# MK12.net
KiCad netlist of a schematic drawn in EAGLE
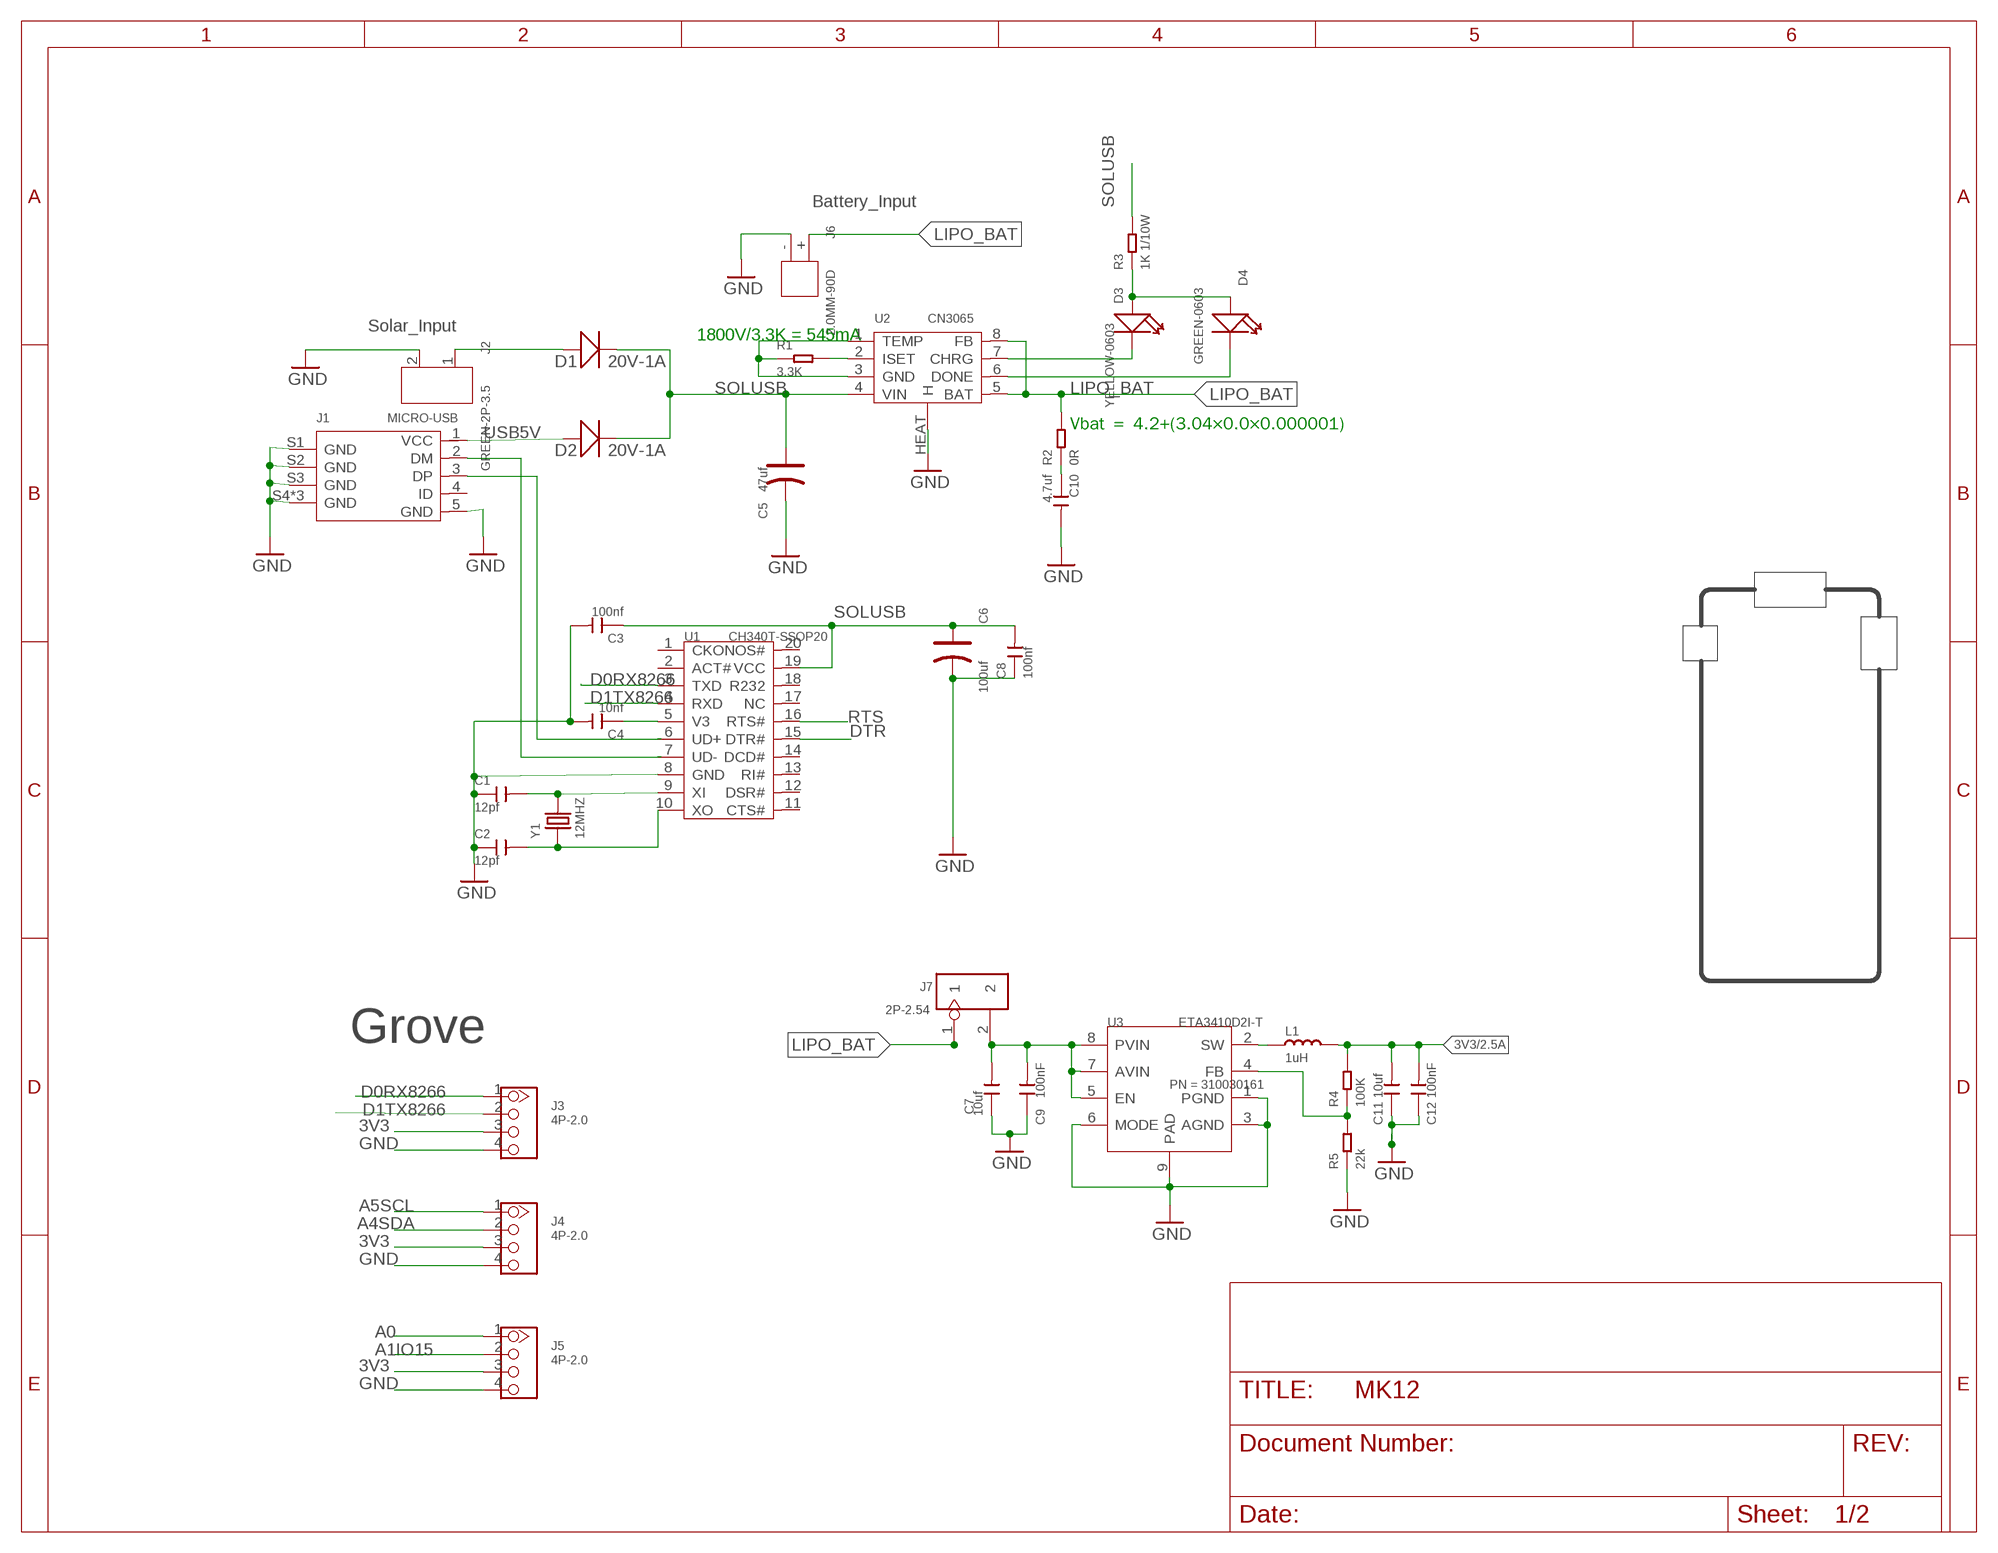
[diagram p0: schematic, sheet 1]
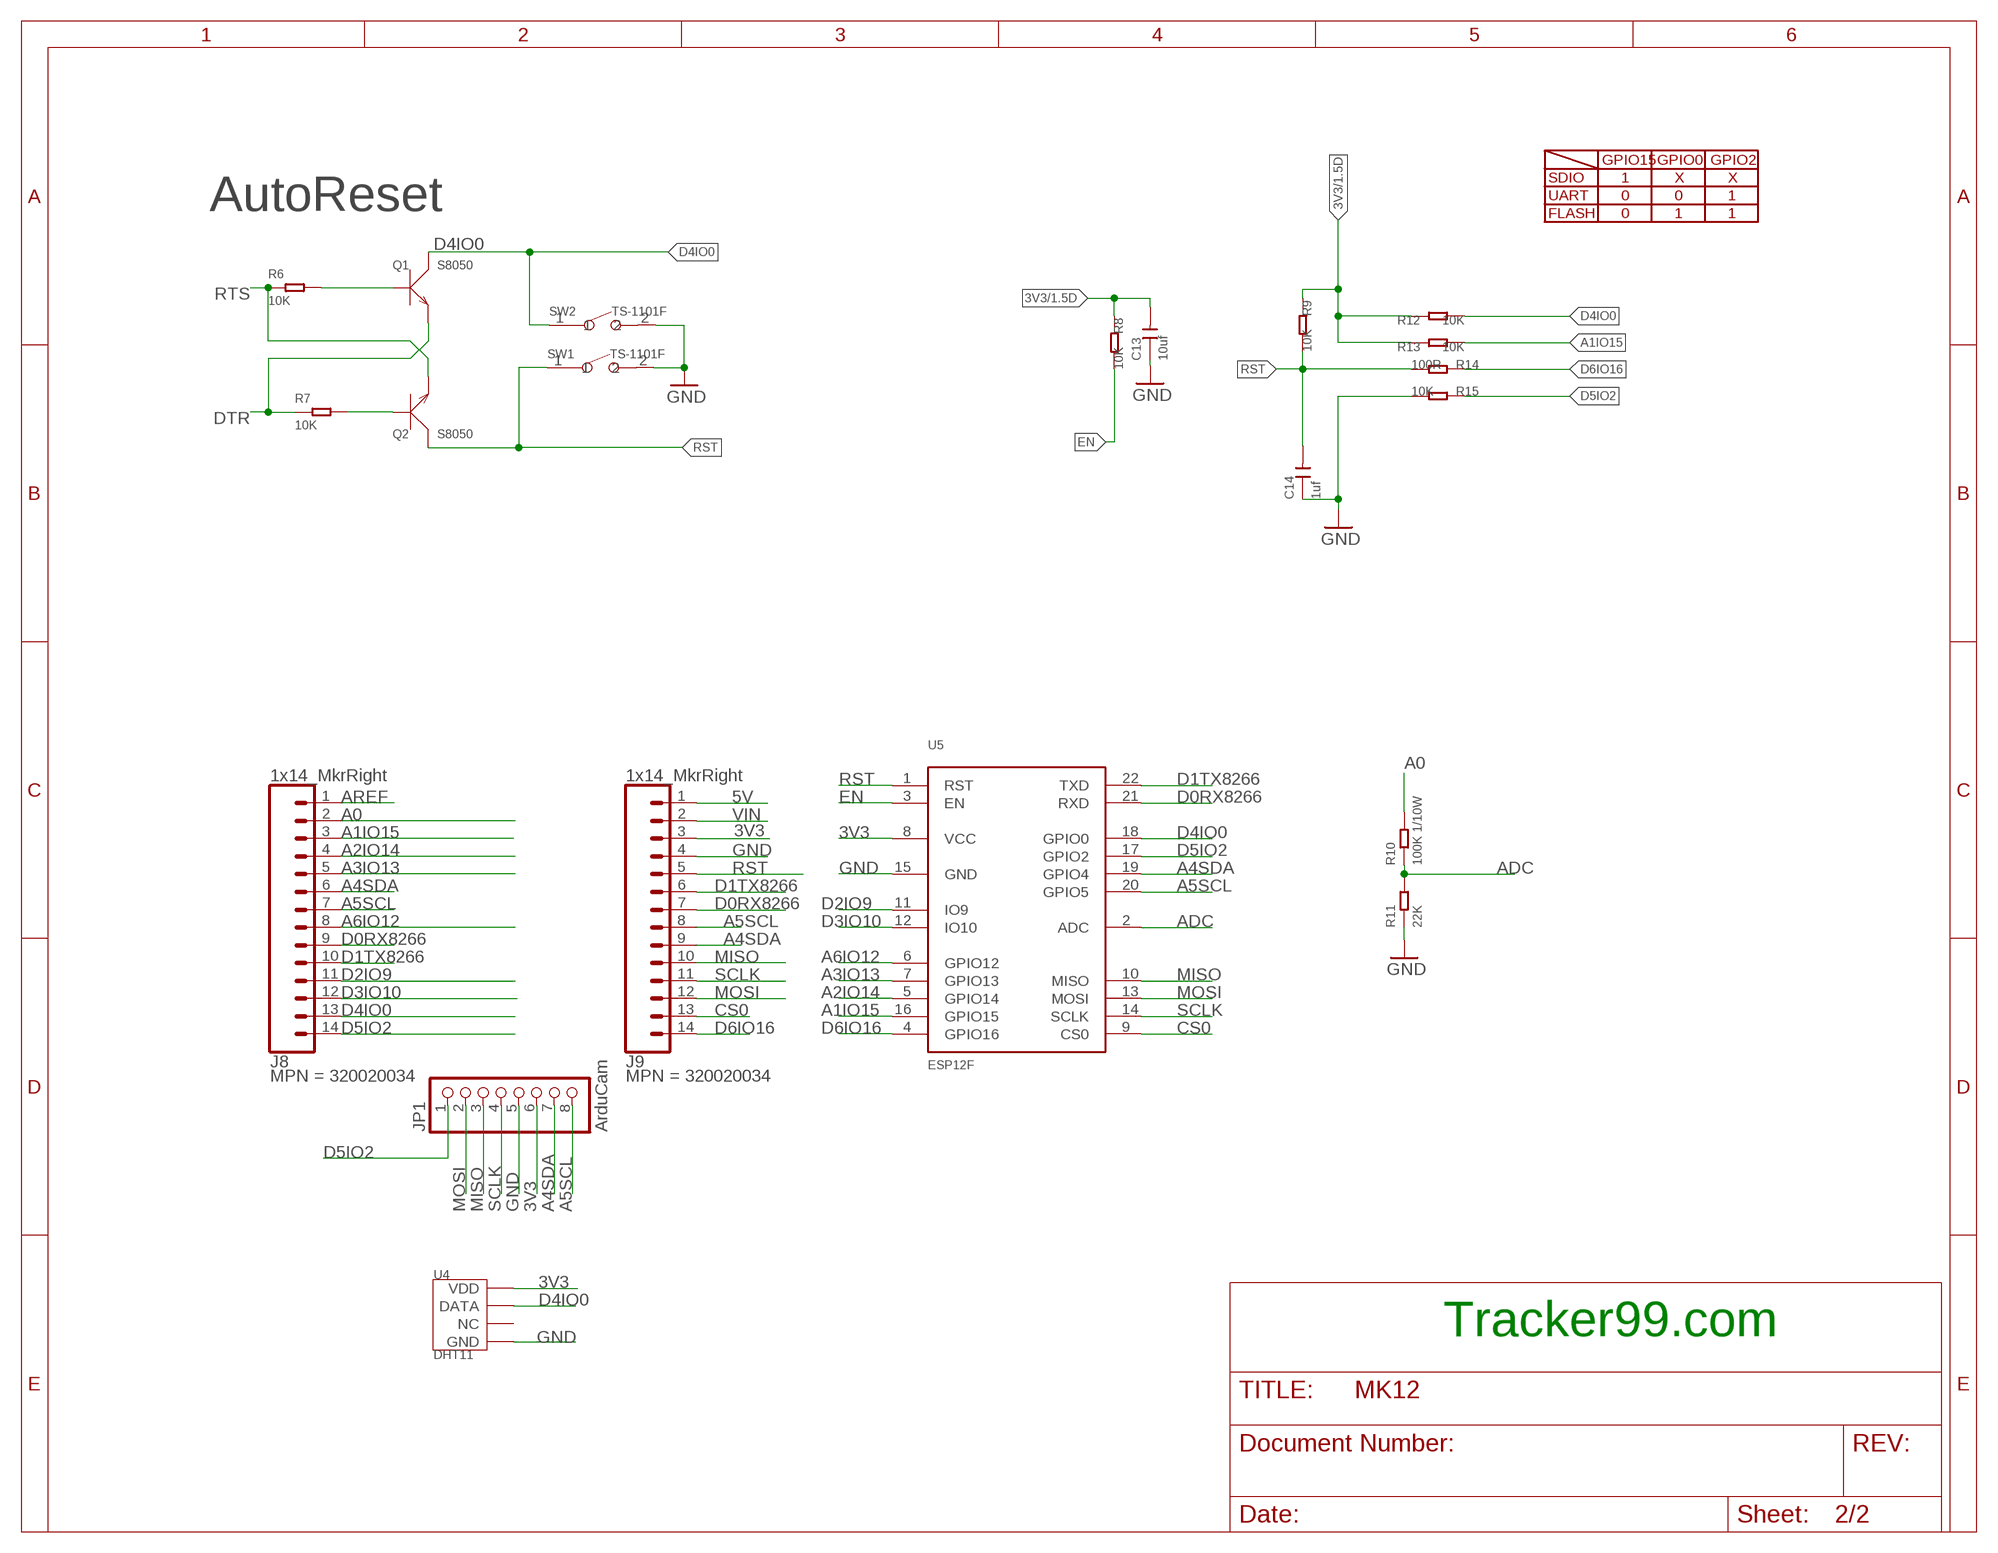
[diagram p1: schematic, sheet 2]

(export (version "E")
  (design (tool "Eeschema 10.0.6"))
  (components
    (comp (ref "C1")
      (value "12pf")
      (footprint "eagle-import:C0402")
      (fields (field (name "MPN") "CC0402JRNPO9BN120"))
      (libsource (lib "eagle-import") (part "CERAMIC-12PF-50V-5%-NPO(0402)"))
    )
    (comp (ref "C2")
      (value "12pf")
      (footprint "eagle-import:C0402")
      (fields (field (name "MPN") "CC0402JRNPO9BN120"))
      (libsource (lib "eagle-import") (part "CERAMIC-12PF-50V-5%-NPO(0402)"))
    )
    (comp (ref "C3")
      (value "100nf")
      (footprint "eagle-import:C0603")
      (fields (field (name "MPN") "CC0603KRX7R9BB104"))
      (libsource (lib "eagle-import") (part "CERAMIC-100NF-50V-10%-X7R(0603)"))
    )
    (comp (ref "C4")
      (value "10nf")
      (footprint "eagle-import:C0603")
      (fields (field (name "MPN") "CC0603KRX7R9BB103"))
      (libsource (lib "eagle-import") (part "CERAMIC-10NF-50V-10%-X7R(0603)"))
    )
    (comp (ref "C5")
      (value "47uf")
      (footprint "eagle-import:AVX-A")
      (fields (field (name "MPN") "TAJA476*006#NJ"))
      (libsource (lib "eagle-import") (part "TANTALUM-SMD-47UF-6.3V(AVX-A)"))
    )
    (comp (ref "C6")
      (value "100uf")
      (footprint "eagle-import:AVX-B")
      (fields (field (name "MPN") "TAJB107M010#NJ"))
      (libsource (lib "eagle-import") (part "TANTALUM-SMD-100UF-10V(AVX-B)"))
    )
    (comp (ref "C7")
      (value "10uf")
      (footprint "eagle-import:C0805")
      (fields (field (name "MPN") "CC0805KKX5R8BB106"))
      (libsource (lib "eagle-import") (part "CERAMIC-10UF-25V-10%-X5R(0805)"))
    )
    (comp (ref "C8")
      (value "100nf")
      (footprint "eagle-import:C0603")
      (fields (field (name "MPN") "CC0603KRX7R9BB104"))
      (libsource (lib "eagle-import") (part "CERAMIC-100NF-50V-10%-X7R(0603)"))
    )
    (comp (ref "C9")
      (value "100nF")
      (footprint "eagle-import:C0402")
      (libsource (lib "eagle-import") (part "CAP-0402"))
    )
    (comp (ref "C10")
      (value "4.7uf")
      (footprint "eagle-import:C0603")
      (fields (field (name "MPN") "CC0603KRX5R6BB475"))
      (libsource (lib "eagle-import") (part "CERAMIC-4.7UF-10V-10%-X5R(0603)"))
    )
    (comp (ref "C11")
      (value "10uf")
      (footprint "eagle-import:C0805")
      (fields (field (name "MPN") "CC0805KKX5R8BB106"))
      (libsource (lib "eagle-import") (part "CERAMIC-10UF-25V-10%-X5R(0805)"))
    )
    (comp (ref "C12")
      (value "100nF")
      (footprint "eagle-import:C0402")
      (libsource (lib "eagle-import") (part "CAP-0402"))
    )
    (comp (ref "D1")
      (value "20V-1A")
      (footprint "eagle-import:SOD-123")
      (fields (field (name "MPN") "B5819W"))
      (libsource (lib "eagle-import") (part "SMD-DIODE-SCHOTTKY-20V-1A(SOD-123)"))
    )
    (comp (ref "D2")
      (value "20V-1A")
      (footprint "eagle-import:SOD-123")
      (fields (field (name "MPN") "B5819W"))
      (libsource (lib "eagle-import") (part "SMD-DIODE-SCHOTTKY-20V-1A(SOD-123)"))
    )
    (comp (ref "D3")
      (value "YELLOW-0603")
      (footprint "eagle-import:LED-0603")
      (fields (field (name "MPN") "19-217-Y5C-AM1N1VY-3T"))
      (libsource (lib "eagle-import") (part "SMD-LED-CLEAR-YELLOW(0603)"))
    )
    (comp (ref "D4")
      (value "GREEN-0603")
      (footprint "eagle-import:LED-0603")
      (fields (field (name "MPN") "19-217-G7C-AN1P2-3T"))
      (libsource (lib "eagle-import") (part "SMD-LED-CLEAR-GREEN(0603)"))
    )
    (comp (ref "J1")
      (value "MICRO-USB")
      (footprint "eagle-import:MICRO-USB5+4P-SMD-0.65-B")
      (fields (field (name "EAGLEUP") "USB-MICROB;2.54mm"))
      (libsource (lib "eagle-import") (part "MICRO-USB5+4P'5+4P'"))
    )
    (comp (ref "J2")
      (value "GREEN-2P-3.5")
      (footprint "eagle-import:H2-3.5-7.0X7.0MM")
      (libsource (lib "eagle-import") (part "SCREW-TERMINAL-GREEN(2P-3.5)"))
    )
    (comp (ref "J3")
      (value "4P-2.0")
      (footprint "eagle-import:HW4-2.0")
      (libsource (lib "eagle-import") (part "GROVE-CONNECTOR-DIP(4P-2.0)"))
    )
    (comp (ref "J4")
      (value "4P-2.0")
      (footprint "eagle-import:HW4-2.0")
      (libsource (lib "eagle-import") (part "GROVE-CONNECTOR-DIP(4P-2.0)"))
    )
    (comp (ref "J5")
      (value "4P-2.0")
      (footprint "eagle-import:HW4-2.0")
      (libsource (lib "eagle-import") (part "GROVE-CONNECTOR-DIP(4P-2.0)"))
    )
    (comp (ref "J6")
      (value "2.0MM-90D")
      (footprint "eagle-import:H2-2.0-90D")
      (libsource (lib "eagle-import") (part "CONN-HEADER-PH-SIDE-(2P-2.0MM)'90D'"))
    )
    (comp (ref "J7")
      (value "2P-2.54")
      (footprint "eagle-import:H2-2.54")
      (fields (field (name "MPN") "P125-1102A0BS116A3"))
      (libsource (lib "eagle-import") (part "DIP-WHITE-MALE-HEADER-VERT(2P-2.54)"))
    )
    (comp (ref "L1")
      (value "1uH")
      (footprint "eagle-import:L0603")
      (libsource (lib "eagle-import") (part "INDUCTOR/FERRITE-BEAD'0603'"))
    )
    (comp (ref "R1")
      (value "3.3K")
      (footprint "eagle-import:R0603")
      (libsource (lib "eagle-import") (part "SMD-RES-3.3K-5%-1/10W(0603)"))
    )
    (comp (ref "R2")
      (value "0R")
      (footprint "eagle-import:R0603")
      (fields (field (name "MPN") "RC0603JR-070RL"))
      (libsource (lib "eagle-import") (part "SMD-RES-0R-5%-1/10W(0603)"))
    )
    (comp (ref "R3")
      (value "1K 1/10W")
      (footprint "eagle-import:R0603")
      (fields (field (name "MPN") "RC0603JR-071KL"))
      (libsource (lib "eagle-import") (part "SMD-RES-1K-5%-1/10W(0603)"))
    )
    (comp (ref "R4")
      (value "100K")
      (footprint "eagle-import:R0402")
      (fields (field (name "MPN") "RC0402FR-07100KL"))
      (libsource (lib "eagle-import") (part "SMD-RES-100K-1%-1/16W(0402)"))
    )
    (comp (ref "R5")
      (value "22k")
      (footprint "eagle-import:R0402")
      (fields (field (name "MPN") "RC0402FR-0722KL"))
      (libsource (lib "eagle-import") (part "SMD-RES-22K-1%-1/16W(0402)"))
    )
    (comp (ref "U1")
      (value "CH340T-SSOP20")
      (footprint "eagle-import:SSOP20-0.65-7.6X5.2MM")
      (fields (field (name "MPN") "CH340T"))
      (libsource (lib "eagle-import") (part "INTERFACE-CH340T(SSOP20)"))
    )
    (comp (ref "U2")
      (value "CN3065")
      (footprint "eagle-import:DFN-8")
      (libsource (lib "eagle-import") (part "PMIC-CN3065-DFN8"))
    )
    (comp (ref "U3")
      (value "ETA3410D2I-T")
      (footprint "eagle-import:DFN8G-0.5-2X2MM")
      (fields (field (name "PN") "310030161"))
      (libsource (lib "eagle-import") (part "CONVERTER-ETA3410"))
    )
    (comp (ref "Y1")
      (value "12MHZ")
      (footprint "eagle-import:X2-SMD-5.0X3.2X1.3MM")
      (fields (field (name "MPN") "5032/2P"))
      (libsource (lib "eagle-import") (part "SMD-CRYSTAL-12MHZ-20PF-20PPM-40R(2P-5.0X3.2MM)"))
    )
    (comp (ref "C13")
      (value "10uf")
      (footprint "eagle-import:C0603")
      (fields (field (name "MPN") "CC0603KRX5R6BB106"))
      (libsource (lib "eagle-import") (part "CERAMIC-10UF-10V-10%-X5R(0603)"))
    )
    (comp (ref "C14")
      (value "1uf")
      (footprint "eagle-import:C0603")
      (fields (field (name "MPN") "CC0603KRX7R8BB105"))
      (libsource (lib "eagle-import") (part "CERAMIC-1UF-25V-10%-X7R(0603)"))
    )
    (comp (ref "J8")
      (value "1x14_MkrRight")
      (footprint "eagle-import:1X14_LOCK")
      (fields (field (name "MPN") "320020034"))
      (libsource (lib "eagle-import") (part "CONN_14LOCK"))
    )
    (comp (ref "J9")
      (value "1x14_MkrRight")
      (footprint "eagle-import:1X14_LOCK")
      (fields (field (name "MPN") "320020034"))
      (libsource (lib "eagle-import") (part "CONN_14LOCK"))
    )
    (comp (ref "JP1")
      (value "ArduCam")
      (footprint "eagle-import:MILLER_1X08-LOCK")
      (libsource (lib "eagle-import") (part "MILLER_PINHD-1X8LOCK"))
    )
    (comp (ref "Q1")
      (value "S8050")
      (footprint "eagle-import:SOT-23")
      (libsource (lib "eagle-import") (part "SMD-TRANSISTORS-NPN-25V-500MW-S8050(SOT-23)"))
    )
    (comp (ref "Q2")
      (value "S8050")
      (footprint "eagle-import:SOT-23")
      (libsource (lib "eagle-import") (part "SMD-TRANSISTORS-NPN-25V-500MW-S8050(SOT-23)"))
    )
    (comp (ref "R6")
      (value "10K")
      (footprint "eagle-import:R0402")
      (fields (field (name "MPN") "RC0402JR-0710KL"))
      (libsource (lib "eagle-import") (part "SMD-RES-10K-5%-1/(0402)"))
    )
    (comp (ref "R7")
      (value "10K")
      (footprint "eagle-import:R0402")
      (fields (field (name "MPN") "RC0402JR-0710KL"))
      (libsource (lib "eagle-import") (part "SMD-RES-10K-5%-1/(0402)"))
    )
    (comp (ref "R8")
      (value "10K")
      (footprint "eagle-import:SEEED-RESISTOR_R0402")
      (fields (field (name "MPN") "RC0402JR-0710KL"))
      (libsource (lib "eagle-import") (part "SEEED-RESISTOR_SMD-RES-10K-5%-1/(0402)"))
    )
    (comp (ref "R9")
      (value "10K")
      (footprint "eagle-import:SEEED-RESISTOR_R0402")
      (fields (field (name "MPN") "RC0402JR-0710KL"))
      (libsource (lib "eagle-import") (part "SEEED-RESISTOR_SMD-RES-10K-5%-1/(0402)"))
    )
    (comp (ref "R10")
      (value "100K 1/10W")
      (footprint "eagle-import:R0603")
      (fields (field (name "MPN") "RC0603JR-07100KL"))
      (libsource (lib "eagle-import") (part "SMD-RES-100K-5%-1/10W(0603)"))
    )
    (comp (ref "R11")
      (value "22K")
      (footprint "eagle-import:R0603")
      (fields (field (name "MPN") "RC0603JR-0722KL"))
      (libsource (lib "eagle-import") (part "SMD-RES-22K-5%-1/10W(0603)"))
    )
    (comp (ref "R12")
      (value "10K")
      (footprint "eagle-import:SEEED-RESISTOR_R0402")
      (fields (field (name "MPN") "RC0402JR-0710KL"))
      (libsource (lib "eagle-import") (part "SEEED-RESISTOR_SMD-RES-10K-5%-1/(0402)"))
    )
    (comp (ref "R13")
      (value "10K")
      (footprint "eagle-import:SEEED-RESISTOR_R0402")
      (fields (field (name "MPN") "RC0402JR-0710KL"))
      (libsource (lib "eagle-import") (part "SEEED-RESISTOR_SMD-RES-10K-5%-1/(0402)"))
    )
    (comp (ref "R14")
      (value "100R")
      (footprint "eagle-import:R0603")
      (fields (field (name "MPN") "RC0603JR-07100RL"))
      (libsource (lib "eagle-import") (part "SMD-RES-100R-5%-1/10W(0603)"))
    )
    (comp (ref "R15")
      (value "10K")
      (footprint "eagle-import:SEEED-RESISTOR_R0402")
      (fields (field (name "MPN") "RC0402JR-0710KL"))
      (libsource (lib "eagle-import") (part "SEEED-RESISTOR_SMD-RES-10K-5%-1/(0402)"))
    )
    (comp (ref "SW1")
      (value "TS-1101F")
      (footprint "eagle-import:SW2-5.0-6.0X3.0X4.3MM")
      (libsource (lib "eagle-import") (part "DIP-BUTTON(2P-6.0X3.0X4.3MM)-TS-1101F"))
    )
    (comp (ref "SW2")
      (value "TS-1101F")
      (footprint "eagle-import:SW2-5.0-6.0X3.0X4.3MM")
      (libsource (lib "eagle-import") (part "DIP-BUTTON(2P-6.0X3.0X4.3MM)-TS-1101F"))
    )
    (comp (ref "U4")
      (value "DHT11")
      (footprint "eagle-import:SNR4-2.54-15.5X12.0X5.5MM")
      (libsource (lib "eagle-import") (part "TEM-HUM-DHT11(4P-15.5X12.0MM)"))
    )
    (comp (ref "U5")
      (value "ESP12F")
      (footprint "eagle-import:ESP-12F")
      (libsource (lib "eagle-import") (part "ESP-12F"))
    )
  )
  (nets
    (net (code "1") (name "3V3") (class "Default")
      (node (ref "C11") (pin "2") (pinfunction "2_2") (pintype "passive"))
      (node (ref "C12") (pin "2") (pinfunction "2_2") (pintype "passive"))
      (node (ref "C13") (pin "2") (pinfunction "2_2") (pintype "passive"))
      (node (ref "J3") (pin "3") (pinfunction "3_3") (pintype "bidirectional"))
      (node (ref "J4") (pin "3") (pinfunction "3_3") (pintype "bidirectional"))
      (node (ref "J5") (pin "3") (pinfunction "3_3") (pintype "bidirectional"))
      (node (ref "J9") (pin "3") (pinfunction "3_3") (pintype "passive"))
      (node (ref "JP1") (pin "6") (pinfunction "6_6") (pintype "passive"))
      (node (ref "L1") (pin "2") (pinfunction "2_2") (pintype "passive"))
      (node (ref "R12") (pin "1") (pinfunction "1_1") (pintype "passive"))
      (node (ref "R13") (pin "1") (pinfunction "1_1") (pintype "passive"))
      (node (ref "R4") (pin "2") (pinfunction "2_2") (pintype "passive"))
      (node (ref "R8") (pin "1") (pinfunction "1_1") (pintype "passive"))
      (node (ref "R9") (pin "1") (pinfunction "1_1") (pintype "passive"))
      (node (ref "U4") (pin "1") (pinfunction "VDD_1") (pintype "power_in"))
      (node (ref "U5") (pin "8") (pinfunction "VCC_8") (pintype "bidirectional"))
    )
    (net (code "2") (name "5V") (class "Default")
      (node (ref "J9") (pin "1") (pinfunction "1_1") (pintype "passive"))
    )
    (net (code "3") (name "A0") (class "Default")
      (node (ref "J5") (pin "1") (pinfunction "1_1") (pintype "bidirectional"))
      (node (ref "J8") (pin "2") (pinfunction "2_2") (pintype "passive"))
      (node (ref "R10") (pin "2") (pinfunction "2_2") (pintype "passive"))
    )
    (net (code "4") (name "A1IO15") (class "Default")
      (node (ref "J5") (pin "2") (pinfunction "2_2") (pintype "bidirectional"))
      (node (ref "J8") (pin "3") (pinfunction "3_3") (pintype "passive"))
      (node (ref "R13") (pin "2") (pinfunction "2_2") (pintype "passive"))
      (node (ref "U5") (pin "16") (pinfunction "GPIO15_16") (pintype "bidirectional"))
    )
    (net (code "5") (name "A2IO14") (class "Default")
      (node (ref "J8") (pin "4") (pinfunction "4_4") (pintype "passive"))
      (node (ref "U5") (pin "5") (pinfunction "GPIO14_5") (pintype "bidirectional"))
    )
    (net (code "6") (name "A3IO13") (class "Default")
      (node (ref "J8") (pin "5") (pinfunction "5_5") (pintype "passive"))
      (node (ref "U5") (pin "7") (pinfunction "GPIO13_7") (pintype "bidirectional"))
    )
    (net (code "7") (name "A4SDA") (class "Default")
      (node (ref "J4") (pin "2") (pinfunction "2_2") (pintype "bidirectional"))
      (node (ref "J8") (pin "6") (pinfunction "6_6") (pintype "passive"))
      (node (ref "J9") (pin "9") (pinfunction "9_9") (pintype "passive"))
      (node (ref "JP1") (pin "7") (pinfunction "7_7") (pintype "passive"))
      (node (ref "U5") (pin "19") (pinfunction "GPIO4_19") (pintype "bidirectional"))
    )
    (net (code "8") (name "A5SCL") (class "Default")
      (node (ref "J4") (pin "1") (pinfunction "1_1") (pintype "bidirectional"))
      (node (ref "J8") (pin "7") (pinfunction "7_7") (pintype "passive"))
      (node (ref "J9") (pin "8") (pinfunction "8_8") (pintype "passive"))
      (node (ref "JP1") (pin "8") (pinfunction "8_8") (pintype "passive"))
      (node (ref "U5") (pin "20") (pinfunction "GPIO5_20") (pintype "bidirectional"))
    )
    (net (code "9") (name "A6IO12") (class "Default")
      (node (ref "J8") (pin "8") (pinfunction "8_8") (pintype "passive"))
      (node (ref "U5") (pin "6") (pinfunction "GPIO12_6") (pintype "bidirectional"))
    )
    (net (code "10") (name "ADC") (class "Default")
      (node (ref "R10") (pin "1") (pinfunction "1_1") (pintype "passive"))
      (node (ref "R11") (pin "2") (pinfunction "2_2") (pintype "passive"))
      (node (ref "U5") (pin "2") (pinfunction "ADC_2") (pintype "bidirectional"))
    )
    (net (code "11") (name "AREF") (class "Default")
      (node (ref "J8") (pin "1") (pinfunction "1_1") (pintype "passive"))
    )
    (net (code "12") (name "CS0") (class "Default")
      (node (ref "J9") (pin "13") (pinfunction "13_13") (pintype "passive"))
      (node (ref "U5") (pin "9") (pinfunction "CS0_9") (pintype "bidirectional"))
    )
    (net (code "13") (name "D0RX8266") (class "Default")
      (node (ref "J3") (pin "1") (pinfunction "1_1") (pintype "bidirectional"))
      (node (ref "J8") (pin "9") (pinfunction "9_9") (pintype "passive"))
      (node (ref "J9") (pin "7") (pinfunction "7_7") (pintype "passive"))
      (node (ref "U1") (pin "3") (pinfunction "TXD_3") (pintype "output"))
      (node (ref "U5") (pin "21") (pinfunction "RXD_21") (pintype "bidirectional"))
    )
    (net (code "14") (name "D1TX8266") (class "Default")
      (node (ref "J3") (pin "2") (pinfunction "2_2") (pintype "bidirectional"))
      (node (ref "J8") (pin "10") (pinfunction "10_10") (pintype "passive"))
      (node (ref "J9") (pin "6") (pinfunction "6_6") (pintype "passive"))
      (node (ref "U1") (pin "4") (pinfunction "RXD_4") (pintype "input"))
      (node (ref "U5") (pin "22") (pinfunction "TXD_22") (pintype "bidirectional"))
    )
    (net (code "15") (name "D2IO9") (class "Default")
      (node (ref "J8") (pin "11") (pinfunction "11_11") (pintype "passive"))
      (node (ref "U5") (pin "11") (pinfunction "IO9_11") (pintype "bidirectional"))
    )
    (net (code "16") (name "D3IO10") (class "Default")
      (node (ref "J8") (pin "12") (pinfunction "12_12") (pintype "passive"))
      (node (ref "U5") (pin "12") (pinfunction "IO10_12") (pintype "bidirectional"))
    )
    (net (code "17") (name "D4IO0") (class "Default")
      (node (ref "J8") (pin "13") (pinfunction "13_13") (pintype "passive"))
      (node (ref "Q1") (pin "3") (pinfunction "C_3") (pintype "passive"))
      (node (ref "R12") (pin "2") (pinfunction "2_2") (pintype "passive"))
      (node (ref "SW2") (pin "1") (pinfunction "1_1") (pintype "bidirectional"))
      (node (ref "U4") (pin "2") (pinfunction "DATA_2") (pintype "bidirectional"))
      (node (ref "U5") (pin "18") (pinfunction "GPIO0_18") (pintype "bidirectional"))
    )
    (net (code "18") (name "D5IO2") (class "Default")
      (node (ref "J8") (pin "14") (pinfunction "14_14") (pintype "passive"))
      (node (ref "JP1") (pin "1") (pinfunction "1_1") (pintype "passive"))
      (node (ref "R15") (pin "1") (pinfunction "1_1") (pintype "passive"))
      (node (ref "U5") (pin "17") (pinfunction "GPIO2_17") (pintype "bidirectional"))
    )
    (net (code "19") (name "D6IO16") (class "Default")
      (node (ref "J9") (pin "14") (pinfunction "14_14") (pintype "passive"))
      (node (ref "R14") (pin "1") (pinfunction "1_1") (pintype "passive"))
      (node (ref "U5") (pin "4") (pinfunction "GPIO16_4") (pintype "bidirectional"))
    )
    (net (code "20") (name "DTR") (class "Default")
      (node (ref "Q1") (pin "2") (pinfunction "E_2") (pintype "passive"))
      (node (ref "R7") (pin "1") (pinfunction "1_1") (pintype "passive"))
      (node (ref "U1") (pin "15") (pinfunction "DTR#_15") (pintype "output"))
    )
    (net (code "21") (name "EN") (class "Default")
      (node (ref "R8") (pin "2") (pinfunction "2_2") (pintype "passive"))
      (node (ref "U5") (pin "3") (pinfunction "EN_3") (pintype "bidirectional"))
    )
    (net (code "22") (name "GND") (class "Default")
      (node (ref "C1") (pin "1") (pinfunction "1_1") (pintype "passive"))
      (node (ref "C10") (pin "2") (pinfunction "2_2") (pintype "passive"))
      (node (ref "C11") (pin "1") (pinfunction "1_1") (pintype "passive"))
      (node (ref "C12") (pin "1") (pinfunction "1_1") (pintype "passive"))
      (node (ref "C13") (pin "1") (pinfunction "1_1") (pintype "passive"))
      (node (ref "C14") (pin "1") (pinfunction "1_1") (pintype "passive"))
      (node (ref "C2") (pin "1") (pinfunction "1_1") (pintype "passive"))
      (node (ref "C3") (pin "2") (pinfunction "2_2") (pintype "passive"))
      (node (ref "C4") (pin "2") (pinfunction "2_2") (pintype "passive"))
      (node (ref "C5") (pin "-") (pinfunction "-_-") (pintype "passive"))
      (node (ref "C6") (pin "-") (pinfunction "-_-") (pintype "passive"))
      (node (ref "C7") (pin "1") (pinfunction "1_1") (pintype "passive"))
      (node (ref "C8") (pin "1") (pinfunction "1_1") (pintype "passive"))
      (node (ref "C9") (pin "1") (pinfunction "1_1") (pintype "passive"))
      (node (ref "J1") (pin "5") (pinfunction "GND_5") (pintype "bidirectional"))
      (node (ref "J1") (pin "S1") (pinfunction "GND_S1") (pintype "bidirectional"))
      (node (ref "J1") (pin "S2") (pinfunction "GND_S2") (pintype "bidirectional"))
      (node (ref "J1") (pin "S3") (pinfunction "GND_S3") (pintype "bidirectional"))
      (node (ref "J1") (pin "S4") (pinfunction "GND_S4") (pintype "bidirectional"))
      (node (ref "J1") (pin "S5") (pinfunction "GND_S5") (pintype "bidirectional"))
      (node (ref "J1") (pin "S6") (pinfunction "GND_S6") (pintype "bidirectional"))
      (node (ref "J2") (pin "2") (pinfunction "2_2") (pintype "bidirectional"))
      (node (ref "J3") (pin "4") (pinfunction "4_4") (pintype "bidirectional"))
      (node (ref "J4") (pin "4") (pinfunction "4_4") (pintype "bidirectional"))
      (node (ref "J5") (pin "4") (pinfunction "4_4") (pintype "bidirectional"))
      (node (ref "J6") (pin "-") (pinfunction "P$2_-") (pintype "bidirectional"))
      (node (ref "J9") (pin "4") (pinfunction "4_4") (pintype "passive"))
      (node (ref "JP1") (pin "5") (pinfunction "5_5") (pintype "passive"))
      (node (ref "R1") (pin "1") (pinfunction "1_1") (pintype "passive"))
      (node (ref "R11") (pin "1") (pinfunction "1_1") (pintype "passive"))
      (node (ref "R15") (pin "2") (pinfunction "2_2") (pintype "passive"))
      (node (ref "R5") (pin "1") (pinfunction "1_1") (pintype "passive"))
      (node (ref "SW1") (pin "2") (pinfunction "2_2") (pintype "bidirectional"))
      (node (ref "SW2") (pin "2") (pinfunction "2_2") (pintype "bidirectional"))
      (node (ref "U1") (pin "8") (pinfunction "GND_8") (pintype "power_in"))
      (node (ref "U2") (pin "1") (pinfunction "TEMP_1") (pintype "input"))
      (node (ref "U2") (pin "3") (pinfunction "GND_3") (pintype "power_in"))
      (node (ref "U2") (pin "HEAT") (pinfunction "H_HEAT") (pintype "bidirectional"))
      (node (ref "U3") (pin "1") (pinfunction "PGND_1") (pintype "bidirectional"))
      (node (ref "U3") (pin "3") (pinfunction "AGND_3") (pintype "bidirectional"))
      (node (ref "U3") (pin "6") (pinfunction "MODE_6") (pintype "bidirectional"))
      (node (ref "U3") (pin "9") (pinfunction "PAD_9") (pintype "bidirectional"))
      (node (ref "U4") (pin "4") (pinfunction "GND_4") (pintype "power_in"))
      (node (ref "U5") (pin "15") (pinfunction "GND_15") (pintype "bidirectional"))
    )
    (net (code "23") (name "LIPO_BAT") (class "Default")
      (node (ref "J6") (pin "+") (pinfunction "P$1_+") (pintype "bidirectional"))
      (node (ref "J7") (pin "1") (pinfunction "1_1") (pintype "bidirectional"))
      (node (ref "R2") (pin "2") (pinfunction "2_2") (pintype "passive"))
      (node (ref "U2") (pin "5") (pinfunction "BAT_5") (pintype "bidirectional"))
      (node (ref "U2") (pin "8") (pinfunction "FB_8") (pintype "input"))
    )
    (net (code "24") (name "MISO") (class "Default")
      (node (ref "J9") (pin "10") (pinfunction "10_10") (pintype "passive"))
      (node (ref "JP1") (pin "3") (pinfunction "3_3") (pintype "passive"))
      (node (ref "U5") (pin "10") (pinfunction "MISO_10") (pintype "bidirectional"))
    )
    (net (code "25") (name "MOSI") (class "Default")
      (node (ref "J9") (pin "12") (pinfunction "12_12") (pintype "passive"))
      (node (ref "JP1") (pin "2") (pinfunction "2_2") (pintype "passive"))
      (node (ref "U5") (pin "13") (pinfunction "MOSI_13") (pintype "bidirectional"))
    )
    (net (code "26") (name "NOS#") (class "Default")
      (node (ref "U1") (pin "20") (pinfunction "NOS#_20") (pintype "power_in"))
    )
    (net (code "27") (name "Net-(C10-Pad1)") (class "Default")
      (node (ref "C10") (pin "1") (pinfunction "1_1") (pintype "passive"))
      (node (ref "R2") (pin "1") (pinfunction "1_1") (pintype "passive"))
    )
    (net (code "28") (name "Net-(D1-Pad+)") (class "Default")
      (node (ref "D1") (pin "+") (pinfunction "+_+") (pintype "passive"))
      (node (ref "J2") (pin "1") (pinfunction "1_1") (pintype "bidirectional"))
    )
    (net (code "29") (name "Net-(D3-Pad+)") (class "Default")
      (node (ref "D3") (pin "+") (pinfunction "+_+") (pintype "passive"))
      (node (ref "D4") (pin "+") (pinfunction "+_+") (pintype "passive"))
      (node (ref "R3") (pin "1") (pinfunction "1_1") (pintype "passive"))
    )
    (net (code "30") (name "Net-(J1-DM)") (class "Default")
      (node (ref "J1") (pin "2") (pinfunction "DM_2") (pintype "bidirectional"))
      (node (ref "U1") (pin "7") (pinfunction "UD-_7") (pintype "bidirectional"))
    )
    (net (code "31") (name "Net-(J1-DP)") (class "Default")
      (node (ref "J1") (pin "3") (pinfunction "DP_3") (pintype "bidirectional"))
      (node (ref "U1") (pin "6") (pinfunction "UD+_6") (pintype "bidirectional"))
    )
    (net (code "32") (name "Net-(Q1-B)") (class "Default")
      (node (ref "Q1") (pin "1") (pinfunction "B_1") (pintype "passive"))
      (node (ref "R6") (pin "2") (pinfunction "2_2") (pintype "passive"))
    )
    (net (code "33") (name "Net-(Q2-B)") (class "Default")
      (node (ref "Q2") (pin "1") (pinfunction "B_1") (pintype "passive"))
      (node (ref "R7") (pin "2") (pinfunction "2_2") (pintype "passive"))
    )
    (net (code "34") (name "Net-(U1-V3)") (class "Default")
      (node (ref "C4") (pin "1") (pinfunction "1_1") (pintype "passive"))
      (node (ref "U1") (pin "5") (pinfunction "V3_5") (pintype "power_in"))
    )
    (net (code "35") (name "Net-(U1-XI)") (class "Default")
      (node (ref "C1") (pin "2") (pinfunction "2_2") (pintype "passive"))
      (node (ref "U1") (pin "9") (pinfunction "XI_9") (pintype "input"))
      (node (ref "Y1") (pin "2") (pinfunction "2_2") (pintype "passive"))
    )
    (net (code "36") (name "Net-(U1-XO)") (class "Default")
      (node (ref "C2") (pin "2") (pinfunction "2_2") (pintype "passive"))
      (node (ref "U1") (pin "10") (pinfunction "XO_10") (pintype "output"))
      (node (ref "Y1") (pin "1") (pinfunction "1_1") (pintype "passive"))
    )
    (net (code "37") (name "Net-(U2-CHRG)") (class "Default")
      (node (ref "D3") (pin "-") (pinfunction "-_-") (pintype "passive"))
      (node (ref "U2") (pin "7") (pinfunction "CHRG_7") (pintype "bidirectional"))
    )
    (net (code "38") (name "Net-(U2-DONE)") (class "Default")
      (node (ref "D4") (pin "-") (pinfunction "-_-") (pintype "passive"))
      (node (ref "U2") (pin "6") (pinfunction "DONE_6") (pintype "bidirectional"))
    )
    (net (code "39") (name "Net-(U2-ISET)") (class "Default")
      (node (ref "R1") (pin "2") (pinfunction "2_2") (pintype "passive"))
      (node (ref "U2") (pin "2") (pinfunction "ISET_2") (pintype "bidirectional"))
    )
    (net (code "40") (name "Net-(U3-AVIN)") (class "Default")
      (node (ref "C7") (pin "2") (pinfunction "2_2") (pintype "passive"))
      (node (ref "C9") (pin "2") (pinfunction "2_2") (pintype "passive"))
      (node (ref "J7") (pin "2") (pinfunction "2_2") (pintype "bidirectional"))
      (node (ref "U3") (pin "5") (pinfunction "EN_5") (pintype "bidirectional"))
      (node (ref "U3") (pin "7") (pinfunction "AVIN_7") (pintype "bidirectional"))
      (node (ref "U3") (pin "8") (pinfunction "PVIN_8") (pintype "bidirectional"))
    )
    (net (code "41") (name "Net-(U3-FB)") (class "Default")
      (node (ref "R4") (pin "1") (pinfunction "1_1") (pintype "passive"))
      (node (ref "R5") (pin "2") (pinfunction "2_2") (pintype "passive"))
      (node (ref "U3") (pin "4") (pinfunction "FB_4") (pintype "bidirectional"))
    )
    (net (code "42") (name "Net-(U3-SW)") (class "Default")
      (node (ref "L1") (pin "1") (pinfunction "1_1") (pintype "passive"))
      (node (ref "U3") (pin "2") (pinfunction "SW_2") (pintype "bidirectional"))
    )
    (net (code "43") (name "RST") (class "Default")
      (node (ref "C14") (pin "2") (pinfunction "2_2") (pintype "passive"))
      (node (ref "J9") (pin "5") (pinfunction "5_5") (pintype "passive"))
      (node (ref "Q2") (pin "3") (pinfunction "C_3") (pintype "passive"))
      (node (ref "R14") (pin "2") (pinfunction "2_2") (pintype "passive"))
      (node (ref "R9") (pin "2") (pinfunction "2_2") (pintype "passive"))
      (node (ref "SW1") (pin "1") (pinfunction "1_1") (pintype "bidirectional"))
      (node (ref "U5") (pin "1") (pinfunction "RST_1") (pintype "bidirectional"))
    )
    (net (code "44") (name "RTS") (class "Default")
      (node (ref "Q2") (pin "2") (pinfunction "E_2") (pintype "passive"))
      (node (ref "R6") (pin "1") (pinfunction "1_1") (pintype "passive"))
      (node (ref "U1") (pin "16") (pinfunction "RTS#_16") (pintype "output"))
    )
    (net (code "45") (name "SCLK") (class "Default")
      (node (ref "J9") (pin "11") (pinfunction "11_11") (pintype "passive"))
      (node (ref "JP1") (pin "4") (pinfunction "4_4") (pintype "passive"))
      (node (ref "U5") (pin "14") (pinfunction "SCLK_14") (pintype "bidirectional"))
    )
    (net (code "46") (name "SOLUSB") (class "Default")
      (node (ref "C3") (pin "1") (pinfunction "1_1") (pintype "passive"))
      (node (ref "C5") (pin "+") (pinfunction "+_+") (pintype "passive"))
      (node (ref "C6") (pin "+") (pinfunction "+_+") (pintype "passive"))
      (node (ref "C8") (pin "2") (pinfunction "2_2") (pintype "passive"))
      (node (ref "D1") (pin "-") (pinfunction "-_-") (pintype "passive"))
      (node (ref "D2") (pin "-") (pinfunction "-_-") (pintype "passive"))
      (node (ref "R3") (pin "2") (pinfunction "2_2") (pintype "passive"))
      (node (ref "U1") (pin "19") (pinfunction "VCC_19") (pintype "power_in"))
      (node (ref "U2") (pin "4") (pinfunction "VIN_4") (pintype "input"))
    )
    (net (code "47") (name "USB5V") (class "Default")
      (node (ref "D2") (pin "+") (pinfunction "+_+") (pintype "passive"))
      (node (ref "J1") (pin "1") (pinfunction "VCC_1") (pintype "bidirectional"))
    )
    (net (code "48") (name "VIN") (class "Default")
      (node (ref "J9") (pin "2") (pinfunction "2_2") (pintype "passive"))
    )
    (net (code "49") (name "unconnected-(J1-ID-Pad4)") (class "Default")
      (node (ref "J1") (pin "4") (pinfunction "ID_4") (pintype "bidirectional"))
    )
    (net (code "50") (name "unconnected-(U1-ACT#-Pad2)") (class "Default")
      (node (ref "U1") (pin "2") (pinfunction "ACT#_2") (pintype "output"))
    )
    (net (code "51") (name "unconnected-(U1-CKO-Pad1)") (class "Default")
      (node (ref "U1") (pin "1") (pinfunction "CKO_1") (pintype "output"))
    )
    (net (code "52") (name "unconnected-(U1-CTS#-Pad11)") (class "Default")
      (node (ref "U1") (pin "11") (pinfunction "CTS#_11") (pintype "input"))
    )
    (net (code "53") (name "unconnected-(U1-DCD#-Pad14)") (class "Default")
      (node (ref "U1") (pin "14") (pinfunction "DCD#_14") (pintype "input"))
    )
    (net (code "54") (name "unconnected-(U1-DSR#-Pad12)") (class "Default")
      (node (ref "U1") (pin "12") (pinfunction "DSR#_12") (pintype "input"))
    )
    (net (code "55") (name "unconnected-(U1-NC-Pad17)") (class "Default")
      (node (ref "U1") (pin "17") (pinfunction "NC_17") (pintype "no_connect"))
    )
    (net (code "56") (name "unconnected-(U1-R232-Pad18)") (class "Default")
      (node (ref "U1") (pin "18") (pinfunction "R232_18") (pintype "input"))
    )
    (net (code "57") (name "unconnected-(U1-RI#-Pad13)") (class "Default")
      (node (ref "U1") (pin "13") (pinfunction "RI#_13") (pintype "input"))
    )
    (net (code "58") (name "unconnected-(U4-NC-Pad3)") (class "Default")
      (node (ref "U4") (pin "3") (pinfunction "NC_3") (pintype "no_connect"))
    )
  )
)
